# drv8353_based_bldc_driver_stage.net
KiCad netlist of a schematic drawn in EAGLE
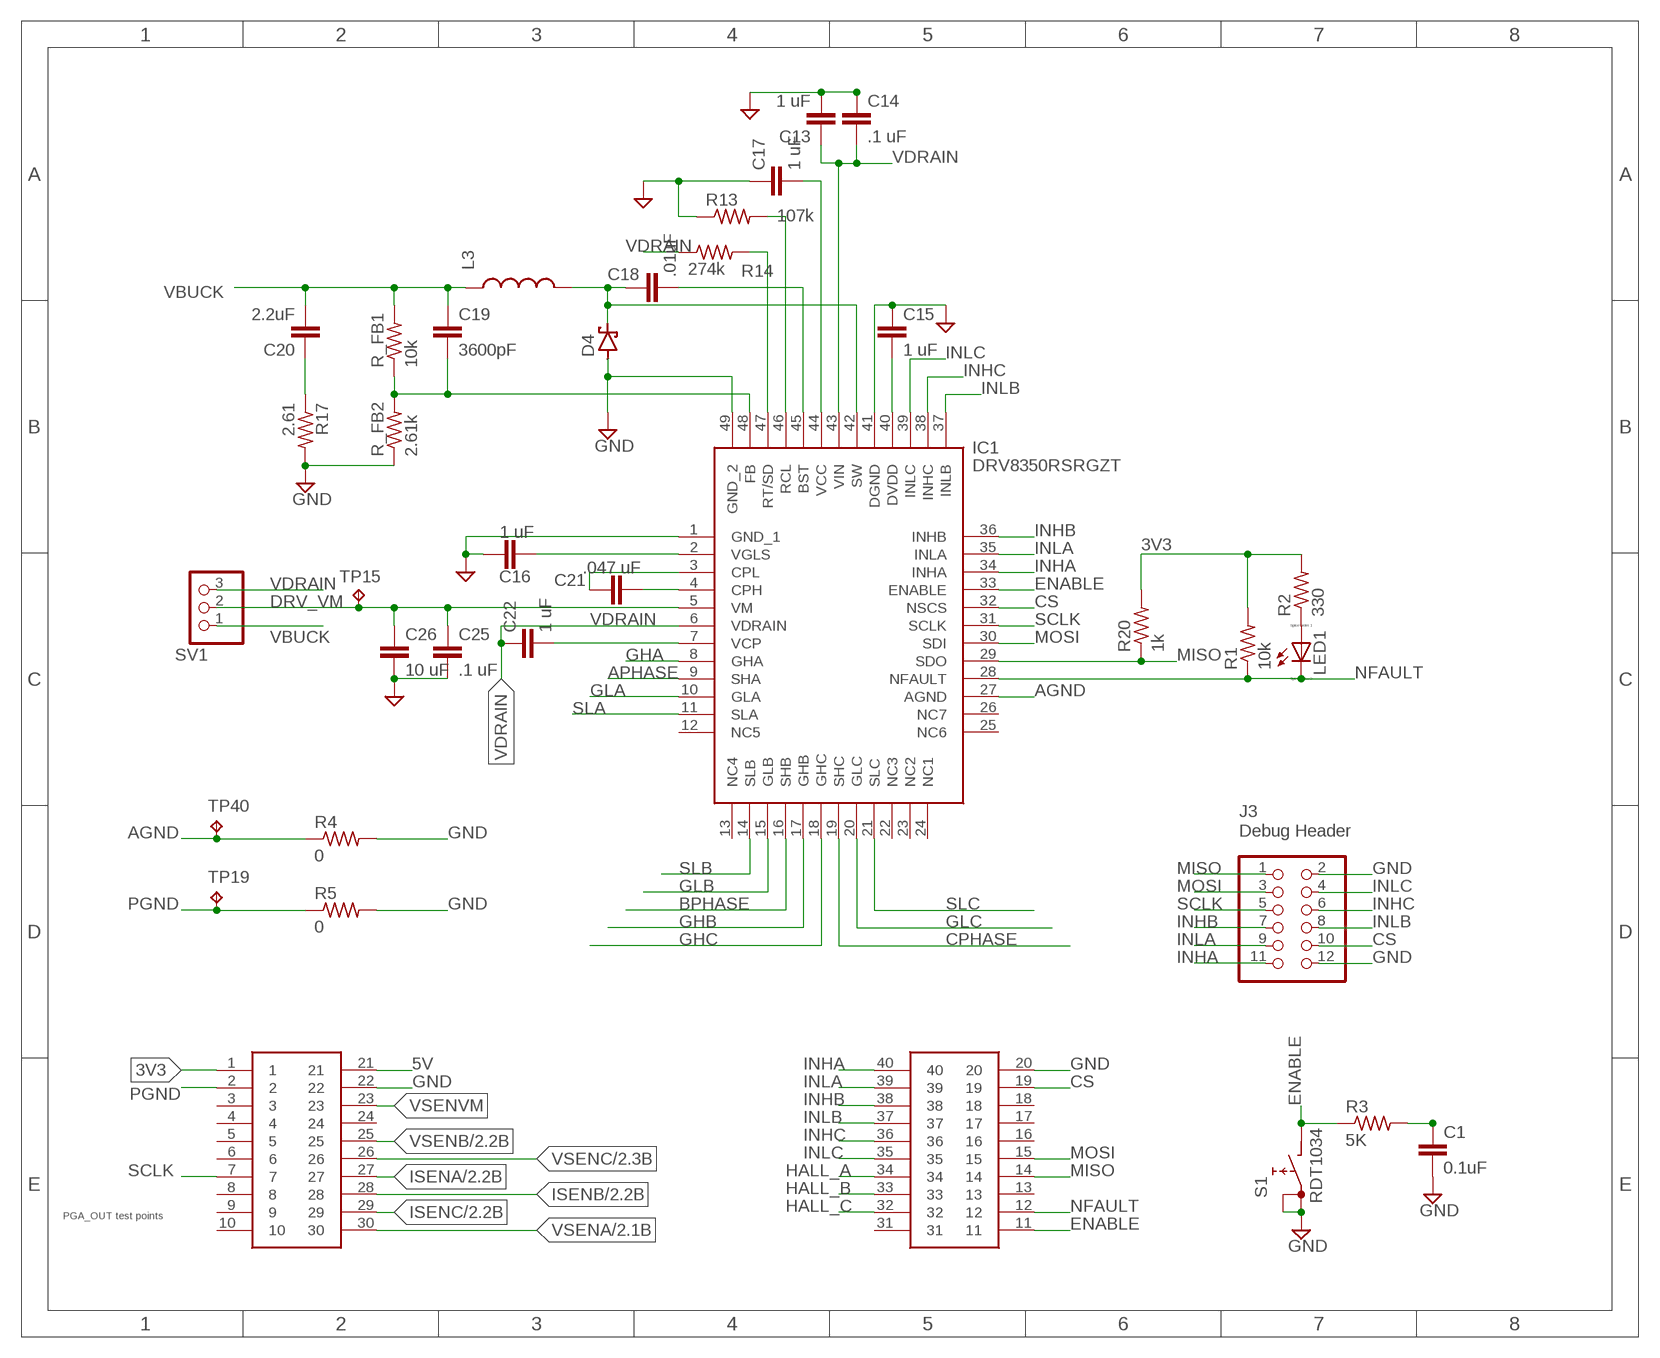
[diagram p0: schematic, sheet 1]
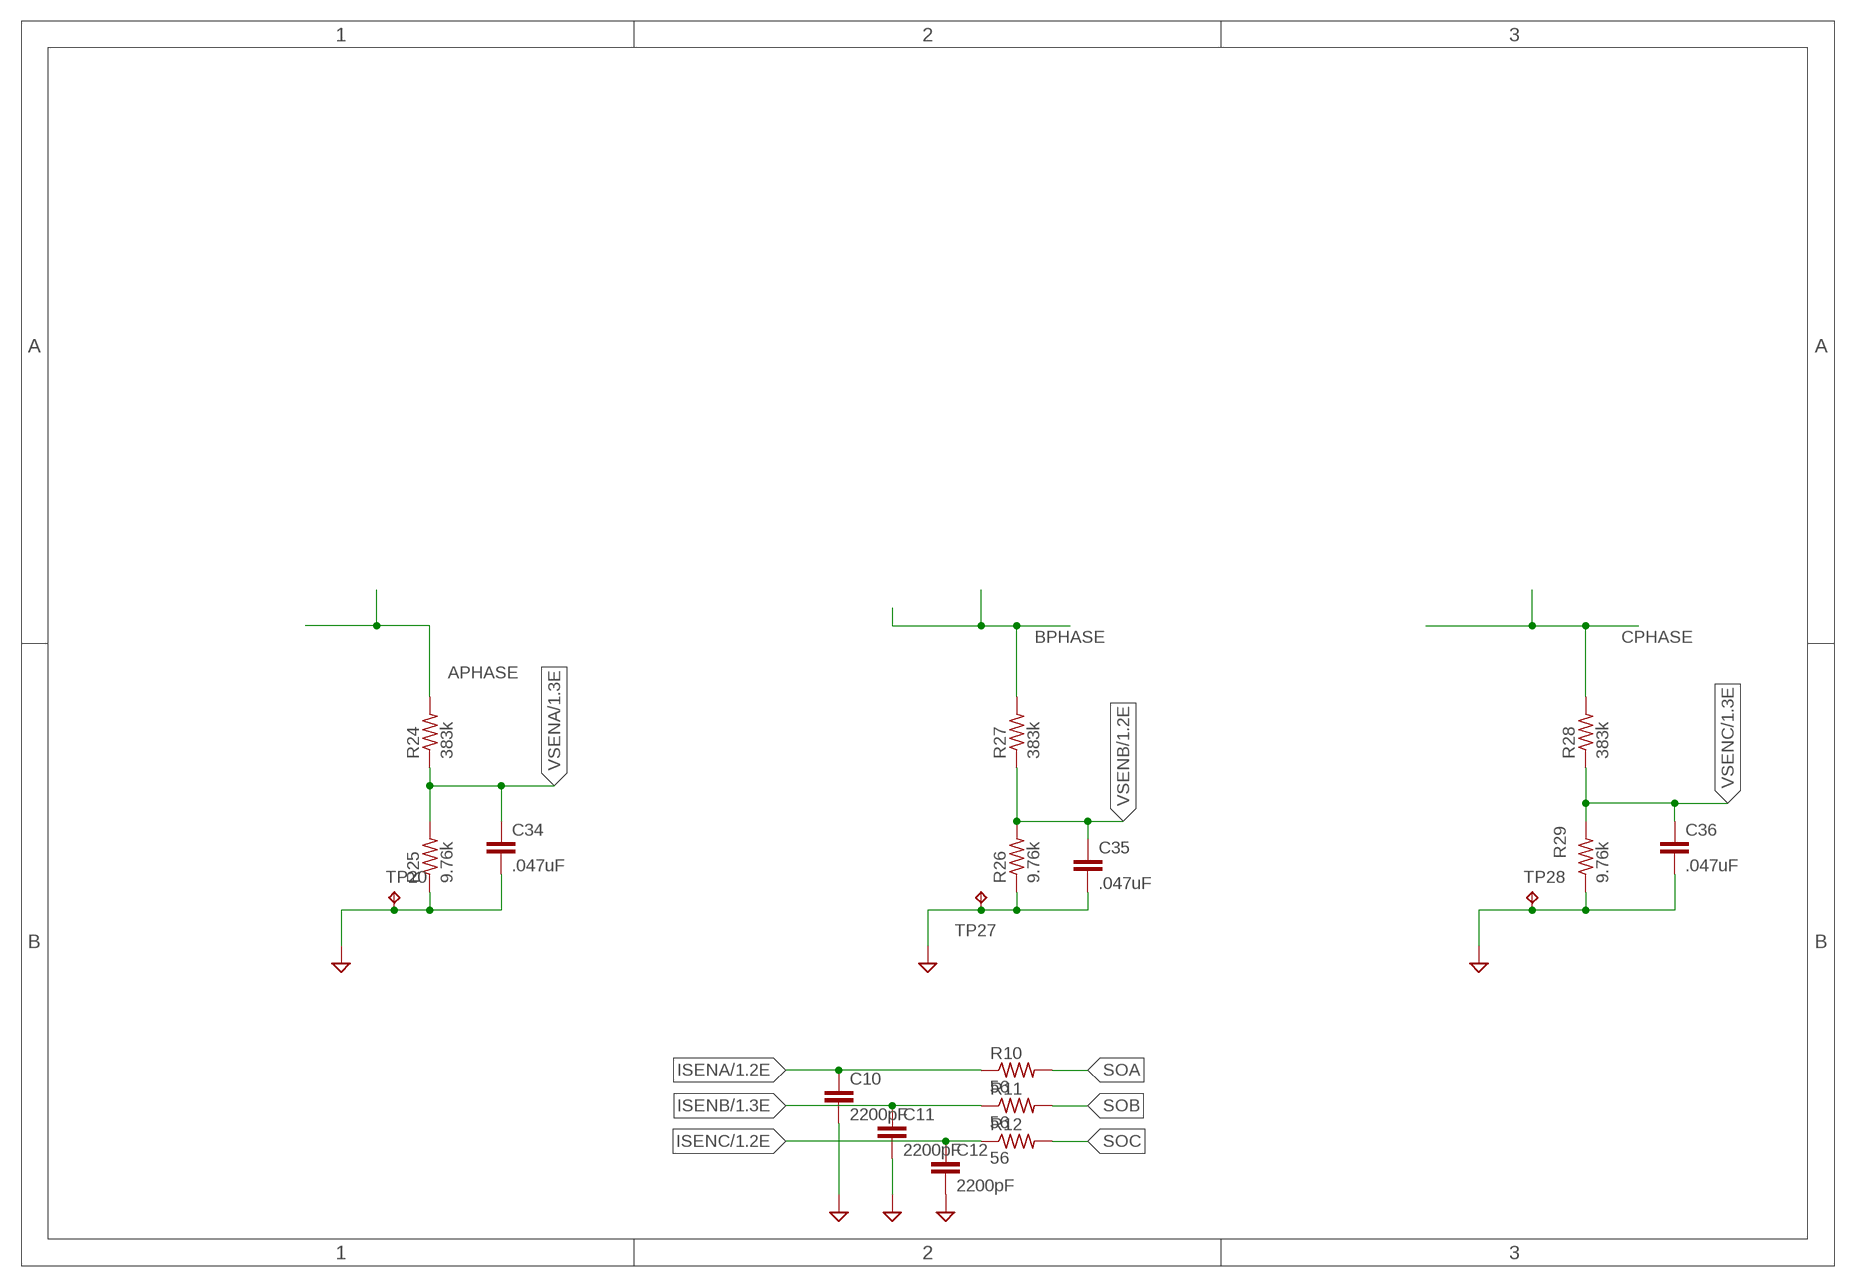
[diagram p1: schematic, sheet 2]
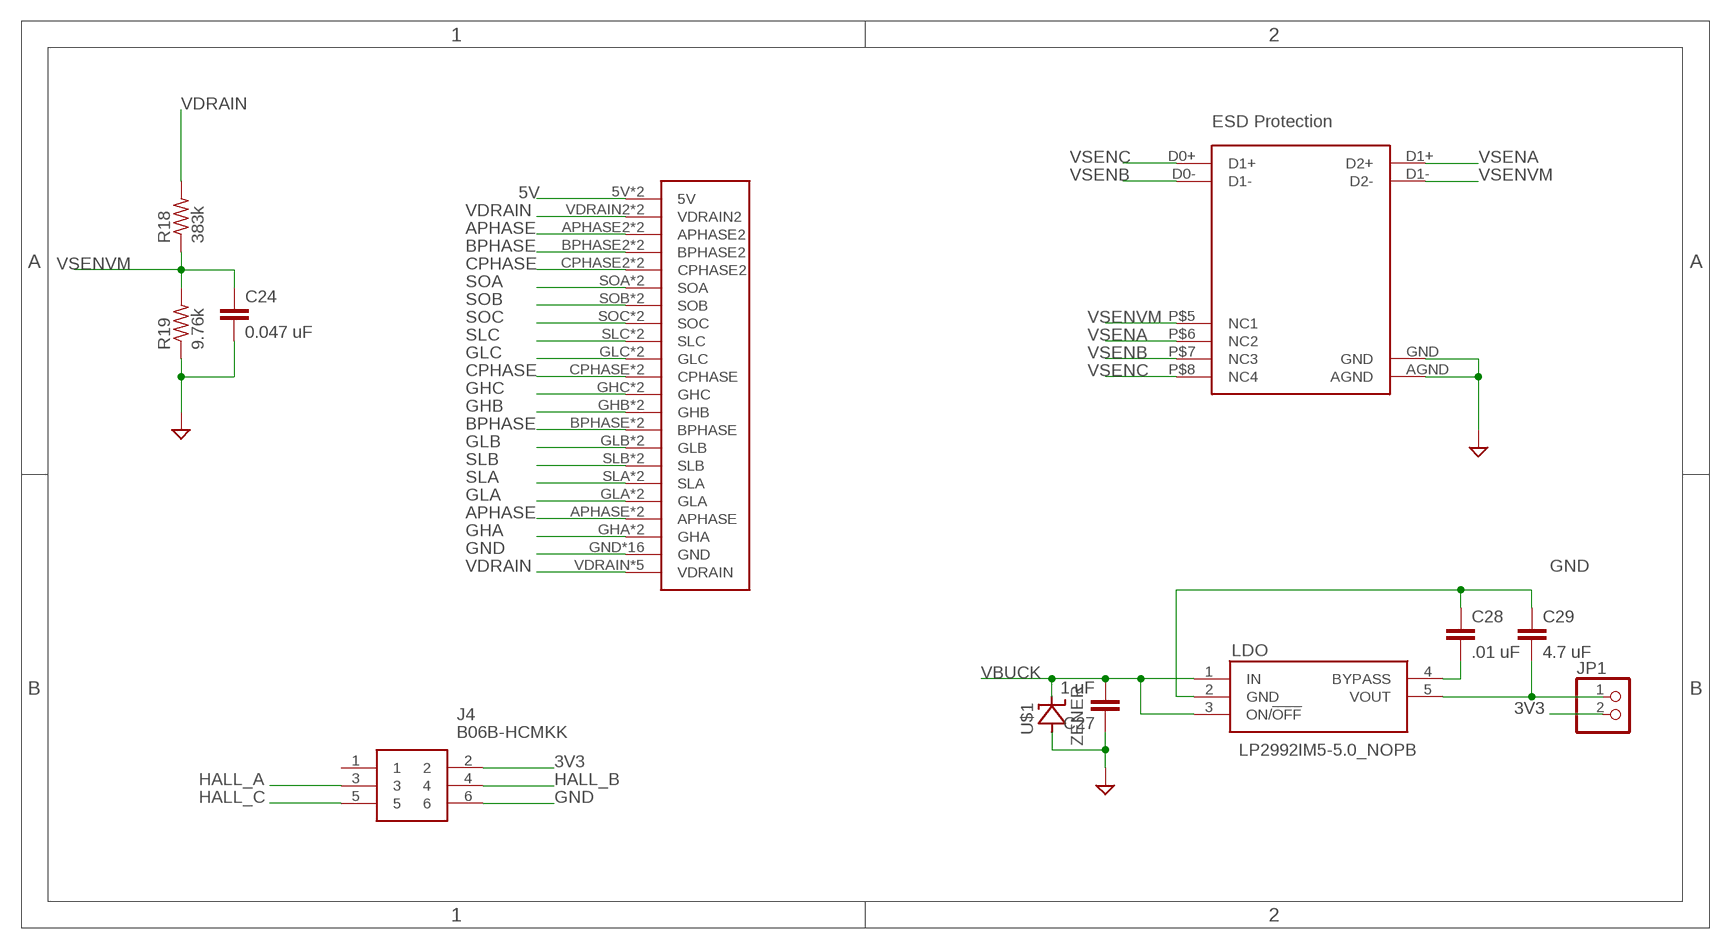
[diagram p2: schematic, sheet 3]

(export (version "E")
  (design (tool "Eeschema 10.0.6"))
  (components
    (comp (ref "C24")
      (value "0.047 uF")
      (footprint "eagle-import:C0603K")
      (libsource (lib "eagle-import") (part "C-EUC0603K"))
    )
    (comp (ref "C27")
      (value "1 uF")
      (footprint "eagle-import:C0805K")
      (libsource (lib "eagle-import") (part "C-EUC0805K"))
    )
    (comp (ref "C28")
      (value ".01 uF")
      (footprint "eagle-import:C0603K")
      (libsource (lib "eagle-import") (part "C-EUC0603K"))
    )
    (comp (ref "C29")
      (value "4.7 uF")
      (footprint "eagle-import:C1210K")
      (libsource (lib "eagle-import") (part "C-EUC1210K"))
    )
    (comp (ref "J4")
      (value "B06B-HCMKK")
      (footprint "eagle-import:B06BHCMKK")
      (fields (field (name "MOUSER_PART_NUMBER") "306-B06B-HCMKK"))
      (libsource (lib "eagle-import") (part "B06B-HCMKK"))
    )
    (comp (ref "JP1")
      (value "PINHD-1X2")
      (footprint "eagle-import:1X02")
      (libsource (lib "eagle-import") (part "PINHD-1X2"))
    )
    (comp (ref "LDO")
      (value "LP2992IM5-5.0_NOPB")
      (footprint "eagle-import:SOT95P280X145-5N")
      (fields
        (field (name "MANUFACTURER_PART_NUMBER") "LP2992IM5-5.0/NOPB")
        (field (name "MOUSER_PART_NUMBER") "926-2992IM5-5.0/NOPB")
      )
      (libsource (lib "eagle-import") (part "LP2992IM5-5.0_NOPB"))
    )
    (comp (ref "R18")
      (value "383k")
      (footprint "eagle-import:R0603")
      (libsource (lib "eagle-import") (part "R-US_R0603"))
    )
    (comp (ref "R19")
      (value "9.76k")
      (footprint "eagle-import:R0603")
      (libsource (lib "eagle-import") (part "R-US_R0603"))
    )
    (comp (ref "TVS_DIODE")
      (value "TPD4S010DQAR")
      (footprint "eagle-import:TPD4S010DQAR")
      (libsource (lib "eagle-import") (part "TPD4S010DQAR"))
    )
    (comp (ref "U$1")
      (value "ZENER")
      (footprint "eagle-import:SOD123")
      (libsource (lib "eagle-import") (part "ZENER"))
    )
    (comp (ref "U$3")
      (value "DRIVER_STAGE_CONNECTORDRIVER")
      (footprint "eagle-import:DRIVER_STAGE_CONNECTION")
      (libsource (lib "eagle-import") (part "DRIVER_STAGE_CONNECTORDRIVER"))
    )
    (comp (ref "C10")
      (value "2200pF")
      (footprint "eagle-import:C0603K")
      (libsource (lib "eagle-import") (part "C-EUC0603K"))
    )
    (comp (ref "C11")
      (value "2200pF")
      (footprint "eagle-import:C0603K")
      (libsource (lib "eagle-import") (part "C-EUC0603K"))
    )
    (comp (ref "C12")
      (value "2200pF")
      (footprint "eagle-import:C0603K")
      (libsource (lib "eagle-import") (part "C-EUC0603K"))
    )
    (comp (ref "C34")
      (value ".047uF")
      (footprint "eagle-import:C0603K")
      (libsource (lib "eagle-import") (part "C-EUC0603K"))
    )
    (comp (ref "C35")
      (value ".047uF")
      (footprint "eagle-import:C0603K")
      (libsource (lib "eagle-import") (part "C-EUC0603K"))
    )
    (comp (ref "C36")
      (value ".047uF")
      (footprint "eagle-import:C0603K")
      (libsource (lib "eagle-import") (part "C-EUC0603K"))
    )
    (comp (ref "R10")
      (value "56")
      (footprint "eagle-import:R0603")
      (libsource (lib "eagle-import") (part "R-US_R0603"))
    )
    (comp (ref "R11")
      (value "56")
      (footprint "eagle-import:R0603")
      (libsource (lib "eagle-import") (part "R-US_R0603"))
    )
    (comp (ref "R12")
      (value "56")
      (footprint "eagle-import:R0603")
      (libsource (lib "eagle-import") (part "R-US_R0603"))
    )
    (comp (ref "R24")
      (value "383k")
      (footprint "eagle-import:R0603")
      (libsource (lib "eagle-import") (part "R-US_R0603"))
    )
    (comp (ref "R25")
      (value "9.76k")
      (footprint "eagle-import:R0603")
      (libsource (lib "eagle-import") (part "R-US_R0603"))
    )
    (comp (ref "R26")
      (value "9.76k")
      (footprint "eagle-import:R0603")
      (libsource (lib "eagle-import") (part "R-US_R0603"))
    )
    (comp (ref "R27")
      (value "383k")
      (footprint "eagle-import:R0603")
      (libsource (lib "eagle-import") (part "R-US_R0603"))
    )
    (comp (ref "R28")
      (value "383k")
      (footprint "eagle-import:R0603")
      (libsource (lib "eagle-import") (part "R-US_R0603"))
    )
    (comp (ref "R29")
      (value "9.76k")
      (footprint "eagle-import:R0603")
      (libsource (lib "eagle-import") (part "R-US_R0603"))
    )
    (comp (ref "TP20")
      (value "TPB1,27")
      (footprint "eagle-import:B1,27")
      (libsource (lib "eagle-import") (part "TPB1,27"))
    )
    (comp (ref "TP27")
      (value "TPB1,27")
      (footprint "eagle-import:B1,27")
      (libsource (lib "eagle-import") (part "TPB1,27"))
    )
    (comp (ref "TP28")
      (value "TPB1,27")
      (footprint "eagle-import:B1,27")
      (libsource (lib "eagle-import") (part "TPB1,27"))
    )
    (comp (ref "C1")
      (value "0.1uF")
      (footprint "eagle-import:C0603K")
      (libsource (lib "eagle-import") (part "resistor_348_C-EUC0603K"))
    )
    (comp (ref "C13")
      (value "1 uF")
      (footprint "eagle-import:C1206K")
      (libsource (lib "eagle-import") (part "C-EUC1206K"))
    )
    (comp (ref "C14")
      (value ".1 uF")
      (footprint "eagle-import:C0805K")
      (libsource (lib "eagle-import") (part "resistor_348_C-EUC0805K"))
    )
    (comp (ref "C15")
      (value "1 uF")
      (footprint "eagle-import:C0603K")
      (libsource (lib "eagle-import") (part "C-EUC0603K"))
    )
    (comp (ref "C16")
      (value "1 uF")
      (footprint "eagle-import:C0603K")
      (libsource (lib "eagle-import") (part "C-EUC0603K"))
    )
    (comp (ref "C17")
      (value "1 uF")
      (footprint "eagle-import:C0603K")
      (libsource (lib "eagle-import") (part "C-EUC0603K"))
    )
    (comp (ref "C18")
      (value ".01uF")
      (footprint "eagle-import:C0603K")
      (libsource (lib "eagle-import") (part "C-EUC0603K"))
    )
    (comp (ref "C19")
      (value "3600pF")
      (footprint "eagle-import:C0603K")
      (libsource (lib "eagle-import") (part "C-EUC0603K"))
    )
    (comp (ref "C20")
      (value "2.2uF")
      (footprint "eagle-import:C0805K")
      (libsource (lib "eagle-import") (part "C-EUC0805K"))
    )
    (comp (ref "C21")
      (value ".047 uF")
      (footprint "eagle-import:C0805K")
      (libsource (lib "eagle-import") (part "C-EUC0805K"))
    )
    (comp (ref "C22")
      (value "1 uF")
      (footprint "eagle-import:C0603K")
      (libsource (lib "eagle-import") (part "resistor_348_C-EUC0603K"))
    )
    (comp (ref "C25")
      (value ".1 uF")
      (footprint "eagle-import:C0805K")
      (libsource (lib "eagle-import") (part "C-EUC0805K"))
    )
    (comp (ref "C26")
      (value "10 uF")
      (footprint "eagle-import:C2220K")
      (libsource (lib "eagle-import") (part "C-EUC2220K"))
    )
    (comp (ref "D4")
      (value "DFLS1200")
      (footprint "eagle-import:DFLS1200")
      (fields (field (name "SPICEPREFIX") "B"))
      (libsource (lib "eagle-import") (part "DFLS1200"))
    )
    (comp (ref "IC1")
      (value "DRV8350RSRGZT")
      (footprint "eagle-import:QFN50P700X700X100-49N")
      (fields
        (field (name "MANUFACTURER_PART_NUMBER") "DRV8353RSRGZT")
        (field (name "MOUSER_PART_NUMBER") "595-DRV8353RSRGZT")
      )
      (libsource (lib "eagle-import") (part "DRV8350RSRGZT"))
    )
    (comp (ref "J3")
      (value "2X6 FEMALE")
      (footprint "eagle-import:2X06")
      (libsource (lib "eagle-import") (part "PINHD-2X6"))
    )
    (comp (ref "L3")
      (value "330 uH")
      (footprint "eagle-import:74404084331")
      (libsource (lib "eagle-import") (part "74404084331"))
    )
    (comp (ref "LED1")
      (value "LED_ESML0603")
      (footprint "eagle-import:LED_SML0603")
      (libsource (lib "eagle-import") (part "LED_ESML0603"))
    )
    (comp (ref "R1")
      (value "10k")
      (footprint "eagle-import:R0603")
      (libsource (lib "eagle-import") (part "R-US_R0603"))
    )
    (comp (ref "R2")
      (value "330")
      (footprint "eagle-import:R0603")
      (libsource (lib "eagle-import") (part "R-US_R0603"))
    )
    (comp (ref "R3")
      (value "5K")
      (footprint "eagle-import:R0603")
      (libsource (lib "eagle-import") (part "resistor_348_R-US_R0603"))
    )
    (comp (ref "R4")
      (value "0")
      (footprint "eagle-import:R0603")
      (libsource (lib "eagle-import") (part "resistor_348_R-US_R0603"))
    )
    (comp (ref "R5")
      (value "0")
      (footprint "eagle-import:R0603")
      (libsource (lib "eagle-import") (part "resistor_348_R-US_R0603"))
    )
    (comp (ref "R13")
      (value "107k")
      (footprint "eagle-import:R0603")
      (libsource (lib "eagle-import") (part "R-US_R0603"))
    )
    (comp (ref "R14")
      (value "274k")
      (footprint "eagle-import:R0603")
      (libsource (lib "eagle-import") (part "R-US_R0603"))
    )
    (comp (ref "R17")
      (value "2.61")
      (footprint "eagle-import:R0603")
      (libsource (lib "eagle-import") (part "R-US_R0603"))
    )
    (comp (ref "R20")
      (value "1k")
      (footprint "eagle-import:R0603")
      (libsource (lib "eagle-import") (part "R-US_R0603"))
    )
    (comp (ref "R_FB1")
      (value "10k")
      (footprint "eagle-import:R0603")
      (libsource (lib "eagle-import") (part "R-US_R0603"))
    )
    (comp (ref "R_FB2")
      (value "2.61k")
      (footprint "eagle-import:R0603")
      (libsource (lib "eagle-import") (part "R-US_R0603"))
    )
    (comp (ref "S1")
      (value "RDT1034")
      (footprint "eagle-import:RDT1034")
      (libsource (lib "eagle-import") (part "RDT1034"))
    )
    (comp (ref "SV1")
      (value "PINHD-1X3")
      (footprint "eagle-import:1X03")
      (libsource (lib "eagle-import") (part "PINHD-1X3"))
    )
    (comp (ref "TP15")
      (value "TPB1,27")
      (footprint "eagle-import:B1,27")
      (libsource (lib "eagle-import") (part "TPB1,27"))
    )
    (comp (ref "TP19")
      (value "TPB1,27")
      (footprint "eagle-import:B1,27")
      (libsource (lib "eagle-import") (part "TPB1,27"))
    )
    (comp (ref "TP40")
      (value "TPB1,27")
      (footprint "eagle-import:B1,27")
      (libsource (lib "eagle-import") (part "TPB1,27"))
    )
    (comp (ref "U$2")
      (value "BOOSTER_DOCK")
      (footprint "eagle-import:BOOSTER_DOCK")
      (libsource (lib "eagle-import") (part "BOOSTER_DOCK"))
    )
  )
  (nets
    (net (code "1") (name "3V3") (class "Default")
      (node (ref "J4") (pin "2") (pinfunction "2_2") (pintype "bidirectional"))
      (node (ref "JP1") (pin "2") (pinfunction "2_2") (pintype "passive"))
      (node (ref "R1") (pin "2") (pinfunction "2_2") (pintype "passive"))
      (node (ref "R2") (pin "2") (pinfunction "2_2") (pintype "passive"))
      (node (ref "R20") (pin "2") (pinfunction "2_2") (pintype "passive"))
      (node (ref "U$2") (pin "1") (pinfunction "1_1") (pintype "bidirectional"))
    )
    (net (code "2") (name "5V") (class "Default")
      (node (ref "U$2") (pin "21") (pinfunction "21_21") (pintype "bidirectional"))
      (node (ref "U$3") (pin "5V") (pinfunction "5V_5V") (pintype "bidirectional"))
      (node (ref "U$3") (pin "5VH") (pinfunction "5V_5VH") (pintype "bidirectional"))
    )
    (net (code "3") (name "AGND") (class "Default")
      (node (ref "IC1") (pin "27") (pinfunction "AGND_27") (pintype "bidirectional"))
      (node (ref "R4") (pin "1") (pinfunction "1_1") (pintype "passive"))
      (node (ref "TP40") (pin "TP") (pinfunction "TP_TP") (pintype "input"))
    )
    (net (code "4") (name "APHASE") (class "Default")
      (node (ref "IC1") (pin "9") (pinfunction "SHA_9") (pintype "bidirectional"))
      (node (ref "R24") (pin "2") (pinfunction "2_2") (pintype "passive"))
      (node (ref "U$3") (pin "APHASE") (pinfunction "APHASE_APHASE") (pintype "bidirectional"))
      (node (ref "U$3") (pin "APHASE2") (pinfunction "APHASE2_APHASE2") (pintype "bidirectional"))
      (node (ref "U$3") (pin "APHASE2H") (pinfunction "APHASE2_APHASE2H") (pintype "bidirectional"))
      (node (ref "U$3") (pin "APHASEH") (pinfunction "APHASE_APHASEH") (pintype "bidirectional"))
    )
    (net (code "5") (name "BPHASE") (class "Default")
      (node (ref "IC1") (pin "16") (pinfunction "SHB_16") (pintype "bidirectional"))
      (node (ref "R27") (pin "2") (pinfunction "2_2") (pintype "passive"))
      (node (ref "U$3") (pin "BPHASE") (pinfunction "BPHASE_BPHASE") (pintype "bidirectional"))
      (node (ref "U$3") (pin "BPHASE2") (pinfunction "BPHASE2_BPHASE2") (pintype "bidirectional"))
      (node (ref "U$3") (pin "BPHASE2H") (pinfunction "BPHASE2_BPHASE2H") (pintype "bidirectional"))
      (node (ref "U$3") (pin "BPHASEH") (pinfunction "BPHASE_BPHASEH") (pintype "bidirectional"))
    )
    (net (code "6") (name "CPHASE") (class "Default")
      (node (ref "IC1") (pin "19") (pinfunction "SHC_19") (pintype "bidirectional"))
      (node (ref "R28") (pin "2") (pinfunction "2_2") (pintype "passive"))
      (node (ref "U$3") (pin "CPHASE") (pinfunction "CPHASE_CPHASE") (pintype "bidirectional"))
      (node (ref "U$3") (pin "CPHASE2") (pinfunction "CPHASE2_CPHASE2") (pintype "bidirectional"))
      (node (ref "U$3") (pin "CPHASE2H") (pinfunction "CPHASE2_CPHASE2H") (pintype "bidirectional"))
      (node (ref "U$3") (pin "CPHASEH") (pinfunction "CPHASE_CPHASEH") (pintype "bidirectional"))
    )
    (net (code "7") (name "CS") (class "Default")
      (node (ref "IC1") (pin "32") (pinfunction "NSCS_32") (pintype "bidirectional"))
      (node (ref "J3") (pin "10") (pinfunction "10_10") (pintype "passive"))
      (node (ref "U$2") (pin "19") (pinfunction "19_19") (pintype "bidirectional"))
    )
    (net (code "8") (name "DRV_VM") (class "Default")
      (node (ref "C25") (pin "1") (pinfunction "1_1") (pintype "passive"))
      (node (ref "C26") (pin "1") (pinfunction "1_1") (pintype "passive"))
      (node (ref "IC1") (pin "5") (pinfunction "VM_5") (pintype "bidirectional"))
      (node (ref "SV1") (pin "2") (pinfunction "2_2") (pintype "passive"))
      (node (ref "TP15") (pin "TP") (pinfunction "TP_TP") (pintype "input"))
    )
    (net (code "9") (name "ENABLE") (class "Default")
      (node (ref "IC1") (pin "33") (pinfunction "ENABLE_33") (pintype "bidirectional"))
      (node (ref "R3") (pin "1") (pinfunction "1_1") (pintype "passive"))
      (node (ref "S1") (pin "B") (pinfunction "B_B") (pintype "passive"))
      (node (ref "U$2") (pin "11") (pinfunction "11_11") (pintype "bidirectional"))
    )
    (net (code "10") (name "GHA") (class "Default")
      (node (ref "IC1") (pin "8") (pinfunction "GHA_8") (pintype "bidirectional"))
      (node (ref "U$3") (pin "GHA") (pinfunction "GHA_GHA") (pintype "bidirectional"))
      (node (ref "U$3") (pin "GHAH") (pinfunction "GHA_GHAH") (pintype "bidirectional"))
    )
    (net (code "11") (name "GHB") (class "Default")
      (node (ref "IC1") (pin "17") (pinfunction "GHB_17") (pintype "bidirectional"))
      (node (ref "U$3") (pin "GHB") (pinfunction "GHB_GHB") (pintype "bidirectional"))
      (node (ref "U$3") (pin "GHBH") (pinfunction "GHB_GHBH") (pintype "bidirectional"))
    )
    (net (code "12") (name "GHC") (class "Default")
      (node (ref "IC1") (pin "18") (pinfunction "GHC_18") (pintype "bidirectional"))
      (node (ref "U$3") (pin "GHC") (pinfunction "GHC_GHC") (pintype "bidirectional"))
      (node (ref "U$3") (pin "GHCH") (pinfunction "GHC_GHCH") (pintype "bidirectional"))
    )
    (net (code "13") (name "GLA") (class "Default")
      (node (ref "IC1") (pin "10") (pinfunction "GLA_10") (pintype "bidirectional"))
      (node (ref "U$3") (pin "GLA") (pinfunction "GLA_GLA") (pintype "bidirectional"))
      (node (ref "U$3") (pin "GLAH") (pinfunction "GLA_GLAH") (pintype "bidirectional"))
    )
    (net (code "14") (name "GLB") (class "Default")
      (node (ref "IC1") (pin "15") (pinfunction "GLB_15") (pintype "bidirectional"))
      (node (ref "U$3") (pin "GLB") (pinfunction "GLB_GLB") (pintype "bidirectional"))
      (node (ref "U$3") (pin "GLBH") (pinfunction "GLB_GLBH") (pintype "bidirectional"))
    )
    (net (code "15") (name "GLC") (class "Default")
      (node (ref "IC1") (pin "20") (pinfunction "GLC_20") (pintype "bidirectional"))
      (node (ref "U$3") (pin "GLC") (pinfunction "GLC_GLC") (pintype "bidirectional"))
      (node (ref "U$3") (pin "GLCH") (pinfunction "GLC_GLCH") (pintype "bidirectional"))
    )
    (net (code "16") (name "GND") (class "Default")
      (node (ref "C1") (pin "2") (pinfunction "2_2") (pintype "passive"))
      (node (ref "C10") (pin "2") (pinfunction "2_2") (pintype "passive"))
      (node (ref "C11") (pin "2") (pinfunction "2_2") (pintype "passive"))
      (node (ref "C12") (pin "2") (pinfunction "2_2") (pintype "passive"))
      (node (ref "C13") (pin "2") (pinfunction "2_2") (pintype "passive"))
      (node (ref "C14") (pin "1") (pinfunction "1_1") (pintype "passive"))
      (node (ref "C15") (pin "1") (pinfunction "1_1") (pintype "passive"))
      (node (ref "C16") (pin "1") (pinfunction "1_1") (pintype "passive"))
      (node (ref "C17") (pin "1") (pinfunction "1_1") (pintype "passive"))
      (node (ref "C24") (pin "2") (pinfunction "2_2") (pintype "passive"))
      (node (ref "C25") (pin "2") (pinfunction "2_2") (pintype "passive"))
      (node (ref "C26") (pin "2") (pinfunction "2_2") (pintype "passive"))
      (node (ref "C27") (pin "1") (pinfunction "1_1") (pintype "passive"))
      (node (ref "C28") (pin "1") (pinfunction "1_1") (pintype "passive"))
      (node (ref "C29") (pin "1") (pinfunction "1_1") (pintype "passive"))
      (node (ref "C34") (pin "2") (pinfunction "2_2") (pintype "passive"))
      (node (ref "C35") (pin "2") (pinfunction "2_2") (pintype "passive"))
      (node (ref "C36") (pin "2") (pinfunction "2_2") (pintype "passive"))
      (node (ref "D4") (pin "GND") (pinfunction "GND_GND") (pintype "passive"))
      (node (ref "IC1") (pin "1") (pinfunction "GND_1_1") (pintype "bidirectional"))
      (node (ref "IC1") (pin "41") (pinfunction "DGND_41") (pintype "bidirectional"))
      (node (ref "IC1") (pin "49") (pinfunction "GND_2_49") (pintype "bidirectional"))
      (node (ref "J3") (pin "12") (pinfunction "12_12") (pintype "passive"))
      (node (ref "J3") (pin "2") (pinfunction "2_2") (pintype "passive"))
      (node (ref "J4") (pin "6") (pinfunction "6_6") (pintype "bidirectional"))
      (node (ref "LDO") (pin "2") (pinfunction "GND_2") (pintype "power_in"))
      (node (ref "R13") (pin "1") (pinfunction "1_1") (pintype "passive"))
      (node (ref "R17") (pin "2") (pinfunction "2_2") (pintype "passive"))
      (node (ref "R19") (pin "1") (pinfunction "1_1") (pintype "passive"))
      (node (ref "R25") (pin "1") (pinfunction "1_1") (pintype "passive"))
      (node (ref "R26") (pin "1") (pinfunction "1_1") (pintype "passive"))
      (node (ref "R29") (pin "1") (pinfunction "1_1") (pintype "passive"))
      (node (ref "R4") (pin "2") (pinfunction "2_2") (pintype "passive"))
      (node (ref "R5") (pin "2") (pinfunction "2_2") (pintype "passive"))
      (node (ref "R_FB2") (pin "1") (pinfunction "1_1") (pintype "passive"))
      (node (ref "S1") (pin "A") (pinfunction "A_A") (pintype "passive"))
      (node (ref "S1") (pin "A1") (pinfunction "A1_A1") (pintype "passive"))
      (node (ref "TP20") (pin "TP") (pinfunction "TP_TP") (pintype "input"))
      (node (ref "TP27") (pin "TP") (pinfunction "TP_TP") (pintype "input"))
      (node (ref "TP28") (pin "TP") (pinfunction "TP_TP") (pintype "input"))
      (node (ref "TVS_DIODE") (pin "AGND") (pinfunction "AGND_AGND") (pintype "bidirectional"))
      (node (ref "TVS_DIODE") (pin "GND") (pinfunction "GND_GND") (pintype "bidirectional"))
      (node (ref "U$1") (pin "2") (pinfunction "A_2") (pintype "passive"))
      (node (ref "U$2") (pin "20") (pinfunction "20_20") (pintype "bidirectional"))
      (node (ref "U$2") (pin "22") (pinfunction "22_22") (pintype "bidirectional"))
      (node (ref "U$3") (pin "GND") (pinfunction "GND_GND") (pintype "bidirectional"))
      (node (ref "U$3") (pin "GND2") (pinfunction "GND_GND2") (pintype "bidirectional"))
      (node (ref "U$3") (pin "GND2H1") (pinfunction "GND_GND2H1") (pintype "bidirectional"))
      (node (ref "U$3") (pin "GND2H10") (pinfunction "GND_GND2H10") (pintype "bidirectional"))
      (node (ref "U$3") (pin "GND2H2") (pinfunction "GND_GND2H2") (pintype "bidirectional"))
      (node (ref "U$3") (pin "GND2H3") (pinfunction "GND_GND2H3") (pintype "bidirectional"))
      (node (ref "U$3") (pin "GND2H4") (pinfunction "GND_GND2H4") (pintype "bidirectional"))
      (node (ref "U$3") (pin "GND2H5") (pinfunction "GND_GND2H5") (pintype "bidirectional"))
      (node (ref "U$3") (pin "GND2H6") (pinfunction "GND_GND2H6") (pintype "bidirectional"))
      (node (ref "U$3") (pin "GND2H7") (pinfunction "GND_GND2H7") (pintype "bidirectional"))
      (node (ref "U$3") (pin "GND2H8") (pinfunction "GND_GND2H8") (pintype "bidirectional"))
      (node (ref "U$3") (pin "GND2H9") (pinfunction "GND_GND2H9") (pintype "bidirectional"))
      (node (ref "U$3") (pin "GNDH1") (pinfunction "GND_GNDH1") (pintype "bidirectional"))
      (node (ref "U$3") (pin "GNDH2") (pinfunction "GND_GNDH2") (pintype "bidirectional"))
      (node (ref "U$3") (pin "GNDH3") (pinfunction "GND_GNDH3") (pintype "bidirectional"))
      (node (ref "U$3") (pin "GNDH4") (pinfunction "GND_GNDH4") (pintype "bidirectional"))
    )
    (net (code "17") (name "HALL_A") (class "Default")
      (node (ref "J4") (pin "3") (pinfunction "3_3") (pintype "bidirectional"))
      (node (ref "U$2") (pin "34") (pinfunction "34_34") (pintype "bidirectional"))
    )
    (net (code "18") (name "HALL_B") (class "Default")
      (node (ref "J4") (pin "4") (pinfunction "4_4") (pintype "bidirectional"))
      (node (ref "U$2") (pin "33") (pinfunction "33_33") (pintype "bidirectional"))
    )
    (net (code "19") (name "HALL_C") (class "Default")
      (node (ref "J4") (pin "5") (pinfunction "5_5") (pintype "bidirectional"))
      (node (ref "U$2") (pin "32") (pinfunction "32_32") (pintype "bidirectional"))
    )
    (net (code "20") (name "INHA") (class "Default")
      (node (ref "IC1") (pin "34") (pinfunction "INHA_34") (pintype "bidirectional"))
      (node (ref "J3") (pin "11") (pinfunction "11_11") (pintype "passive"))
      (node (ref "U$2") (pin "40") (pinfunction "40_40") (pintype "bidirectional"))
    )
    (net (code "21") (name "INHB") (class "Default")
      (node (ref "IC1") (pin "36") (pinfunction "INHB_36") (pintype "bidirectional"))
      (node (ref "J3") (pin "7") (pinfunction "7_7") (pintype "passive"))
      (node (ref "U$2") (pin "38") (pinfunction "38_38") (pintype "bidirectional"))
    )
    (net (code "22") (name "INHC") (class "Default")
      (node (ref "IC1") (pin "38") (pinfunction "INHC_38") (pintype "bidirectional"))
      (node (ref "J3") (pin "6") (pinfunction "6_6") (pintype "passive"))
      (node (ref "U$2") (pin "36") (pinfunction "36_36") (pintype "bidirectional"))
    )
    (net (code "23") (name "INLA") (class "Default")
      (node (ref "IC1") (pin "35") (pinfunction "INLA_35") (pintype "bidirectional"))
      (node (ref "J3") (pin "9") (pinfunction "9_9") (pintype "passive"))
      (node (ref "U$2") (pin "39") (pinfunction "39_39") (pintype "bidirectional"))
    )
    (net (code "24") (name "INLB") (class "Default")
      (node (ref "IC1") (pin "37") (pinfunction "INLB_37") (pintype "bidirectional"))
      (node (ref "J3") (pin "8") (pinfunction "8_8") (pintype "passive"))
      (node (ref "U$2") (pin "37") (pinfunction "37_37") (pintype "bidirectional"))
    )
    (net (code "25") (name "INLC") (class "Default")
      (node (ref "IC1") (pin "39") (pinfunction "INLC_39") (pintype "bidirectional"))
      (node (ref "J3") (pin "4") (pinfunction "4_4") (pintype "passive"))
      (node (ref "U$2") (pin "35") (pinfunction "35_35") (pintype "bidirectional"))
    )
    (net (code "26") (name "ISENA") (class "Default")
      (node (ref "C10") (pin "1") (pinfunction "1_1") (pintype "passive"))
      (node (ref "R10") (pin "1") (pinfunction "1_1") (pintype "passive"))
      (node (ref "U$2") (pin "27") (pinfunction "27_27") (pintype "bidirectional"))
    )
    (net (code "27") (name "ISENB") (class "Default")
      (node (ref "C11") (pin "1") (pinfunction "1_1") (pintype "passive"))
      (node (ref "R11") (pin "1") (pinfunction "1_1") (pintype "passive"))
      (node (ref "U$2") (pin "28") (pinfunction "28_28") (pintype "bidirectional"))
    )
    (net (code "28") (name "ISENC") (class "Default")
      (node (ref "C12") (pin "1") (pinfunction "1_1") (pintype "passive"))
      (node (ref "R12") (pin "1") (pinfunction "1_1") (pintype "passive"))
      (node (ref "U$2") (pin "29") (pinfunction "29_29") (pintype "bidirectional"))
    )
    (net (code "29") (name "MISO") (class "Default")
      (node (ref "IC1") (pin "29") (pinfunction "SDO_29") (pintype "bidirectional"))
      (node (ref "J3") (pin "1") (pinfunction "1_1") (pintype "passive"))
      (node (ref "R20") (pin "1") (pinfunction "1_1") (pintype "passive"))
      (node (ref "U$2") (pin "14") (pinfunction "14_14") (pintype "bidirectional"))
    )
    (net (code "30") (name "MOSI") (class "Default")
      (node (ref "IC1") (pin "30") (pinfunction "SDI_30") (pintype "bidirectional"))
      (node (ref "J3") (pin "3") (pinfunction "3_3") (pintype "passive"))
      (node (ref "U$2") (pin "15") (pinfunction "15_15") (pintype "bidirectional"))
    )
    (net (code "31") (name "NFAULT") (class "Default")
      (node (ref "IC1") (pin "28") (pinfunction "NFAULT_28") (pintype "bidirectional"))
      (node (ref "LED1") (pin "C") (pinfunction "C_C") (pintype "passive"))
      (node (ref "R1") (pin "1") (pinfunction "1_1") (pintype "passive"))
      (node (ref "U$2") (pin "12") (pinfunction "12_12") (pintype "bidirectional"))
    )
    (net (code "32") (name "Net-(C1-Pad1)") (class "Default")
      (node (ref "C1") (pin "1") (pinfunction "1_1") (pintype "passive"))
      (node (ref "R3") (pin "2") (pinfunction "2_2") (pintype "passive"))
    )
    (net (code "33") (name "Net-(C20-Pad1)") (class "Default")
      (node (ref "C20") (pin "1") (pinfunction "1_1") (pintype "passive"))
      (node (ref "R17") (pin "1") (pinfunction "1_1") (pintype "passive"))
    )
    (net (code "34") (name "Net-(IC1-BST)") (class "Default")
      (node (ref "C18") (pin "2") (pinfunction "2_2") (pintype "passive"))
      (node (ref "IC1") (pin "45") (pinfunction "BST_45") (pintype "bidirectional"))
    )
    (net (code "35") (name "Net-(IC1-CPH)") (class "Default")
      (node (ref "C21") (pin "2") (pinfunction "2_2") (pintype "passive"))
      (node (ref "IC1") (pin "4") (pinfunction "CPH_4") (pintype "bidirectional"))
    )
    (net (code "36") (name "Net-(IC1-CPL)") (class "Default")
      (node (ref "C21") (pin "1") (pinfunction "1_1") (pintype "passive"))
      (node (ref "IC1") (pin "3") (pinfunction "CPL_3") (pintype "bidirectional"))
    )
    (net (code "37") (name "Net-(IC1-DVDD)") (class "Default")
      (node (ref "C15") (pin "2") (pinfunction "2_2") (pintype "passive"))
      (node (ref "IC1") (pin "40") (pinfunction "DVDD_40") (pintype "bidirectional"))
    )
    (net (code "38") (name "Net-(IC1-FB)") (class "Default")
      (node (ref "C19") (pin "2") (pinfunction "2_2") (pintype "passive"))
      (node (ref "IC1") (pin "48") (pinfunction "FB_48") (pintype "bidirectional"))
      (node (ref "R_FB1") (pin "1") (pinfunction "1_1") (pintype "passive"))
      (node (ref "R_FB2") (pin "2") (pinfunction "2_2") (pintype "passive"))
    )
    (net (code "39") (name "Net-(IC1-RCL)") (class "Default")
      (node (ref "IC1") (pin "46") (pinfunction "RCL_46") (pintype "bidirectional"))
      (node (ref "R13") (pin "2") (pinfunction "2_2") (pintype "passive"))
    )
    (net (code "40") (name "Net-(IC1-RT{slash}SD)") (class "Default")
      (node (ref "IC1") (pin "47") (pinfunction "RT/SD_47") (pintype "bidirectional"))
      (node (ref "R14") (pin "2") (pinfunction "2_2") (pintype "passive"))
    )
    (net (code "41") (name "Net-(IC1-SW)") (class "Default")
      (node (ref "C18") (pin "1") (pinfunction "1_1") (pintype "passive"))
      (node (ref "D4") (pin "LINE") (pinfunction "LINE_LINE") (pintype "passive"))
      (node (ref "IC1") (pin "42") (pinfunction "SW_42") (pintype "bidirectional"))
      (node (ref "L3") (pin "P$2") (pinfunction "2_P$2") (pintype "passive"))
    )
    (net (code "42") (name "Net-(IC1-VCC)") (class "Default")
      (node (ref "C17") (pin "2") (pinfunction "2_2") (pintype "passive"))
      (node (ref "IC1") (pin "44") (pinfunction "VCC_44") (pintype "bidirectional"))
    )
    (net (code "43") (name "Net-(IC1-VCP)") (class "Default")
      (node (ref "C22") (pin "2") (pinfunction "2_2") (pintype "passive"))
      (node (ref "IC1") (pin "7") (pinfunction "VCP_7") (pintype "bidirectional"))
    )
    (net (code "44") (name "Net-(IC1-VGLS)") (class "Default")
      (node (ref "C16") (pin "2") (pinfunction "2_2") (pintype "passive"))
      (node (ref "IC1") (pin "2") (pinfunction "VGLS_2") (pintype "bidirectional"))
    )
    (net (code "45") (name "Net-(LDO-BYPASS)") (class "Default")
      (node (ref "C28") (pin "2") (pinfunction "2_2") (pintype "passive"))
      (node (ref "LDO") (pin "4") (pinfunction "BYPASS_4") (pintype "bidirectional"))
    )
    (net (code "46") (name "Net-(LDO-VOUT)") (class "Default")
      (node (ref "C29") (pin "2") (pinfunction "2_2") (pintype "passive"))
      (node (ref "JP1") (pin "1") (pinfunction "1_1") (pintype "passive"))
      (node (ref "LDO") (pin "5") (pinfunction "VOUT_5") (pintype "output"))
    )
    (net (code "47") (name "Net-(LED1-PadA)") (class "Default")
      (node (ref "LED1") (pin "A") (pinfunction "A_A") (pintype "passive"))
      (node (ref "R2") (pin "1") (pinfunction "1_1") (pintype "passive"))
    )
    (net (code "48") (name "PGND") (class "Default")
      (node (ref "R5") (pin "1") (pinfunction "1_1") (pintype "passive"))
      (node (ref "TP19") (pin "TP") (pinfunction "TP_TP") (pintype "input"))
      (node (ref "U$2") (pin "2") (pinfunction "2_2") (pintype "bidirectional"))
    )
    (net (code "49") (name "SCLK") (class "Default")
      (node (ref "IC1") (pin "31") (pinfunction "SCLK_31") (pintype "bidirectional"))
      (node (ref "J3") (pin "5") (pinfunction "5_5") (pintype "passive"))
      (node (ref "U$2") (pin "7") (pinfunction "7_7") (pintype "bidirectional"))
    )
    (net (code "50") (name "SLA") (class "Default")
      (node (ref "IC1") (pin "11") (pinfunction "SLA_11") (pintype "bidirectional"))
      (node (ref "U$3") (pin "SLA") (pinfunction "SLA_SLA") (pintype "bidirectional"))
      (node (ref "U$3") (pin "SLAH") (pinfunction "SLA_SLAH") (pintype "bidirectional"))
    )
    (net (code "51") (name "SLB") (class "Default")
      (node (ref "IC1") (pin "14") (pinfunction "SLB_14") (pintype "bidirectional"))
      (node (ref "U$3") (pin "SLB") (pinfunction "SLB_SLB") (pintype "bidirectional"))
      (node (ref "U$3") (pin "SLBH") (pinfunction "SLB_SLBH") (pintype "bidirectional"))
    )
    (net (code "52") (name "SLC") (class "Default")
      (node (ref "IC1") (pin "21") (pinfunction "SLC_21") (pintype "bidirectional"))
      (node (ref "U$3") (pin "SLC") (pinfunction "SLC_SLC") (pintype "bidirectional"))
      (node (ref "U$3") (pin "SLCH") (pinfunction "SLC_SLCH") (pintype "bidirectional"))
    )
    (net (code "53") (name "SOA") (class "Default")
      (node (ref "R10") (pin "2") (pinfunction "2_2") (pintype "passive"))
      (node (ref "U$3") (pin "SOA") (pinfunction "SOA_SOA") (pintype "bidirectional"))
      (node (ref "U$3") (pin "SOAH") (pinfunction "SOA_SOAH") (pintype "bidirectional"))
    )
    (net (code "54") (name "SOB") (class "Default")
      (node (ref "R11") (pin "2") (pinfunction "2_2") (pintype "passive"))
      (node (ref "U$3") (pin "SOB") (pinfunction "SOB_SOB") (pintype "bidirectional"))
      (node (ref "U$3") (pin "SOBH") (pinfunction "SOB_SOBH") (pintype "bidirectional"))
    )
    (net (code "55") (name "SOC") (class "Default")
      (node (ref "R12") (pin "2") (pinfunction "2_2") (pintype "passive"))
      (node (ref "U$3") (pin "SOC") (pinfunction "SOC_SOC") (pintype "bidirectional"))
      (node (ref "U$3") (pin "SOCH") (pinfunction "SOC_SOCH") (pintype "bidirectional"))
    )
    (net (code "56") (name "VBUCK") (class "Default")
      (node (ref "C19") (pin "1") (pinfunction "1_1") (pintype "passive"))
      (node (ref "C20") (pin "2") (pinfunction "2_2") (pintype "passive"))
      (node (ref "C27") (pin "2") (pinfunction "2_2") (pintype "passive"))
      (node (ref "L3") (pin "P$1") (pinfunction "1_P$1") (pintype "passive"))
      (node (ref "LDO") (pin "1") (pinfunction "IN_1") (pintype "input"))
      (node (ref "LDO") (pin "3") (pinfunction "ON/~{OFF}_3") (pintype "bidirectional"))
      (node (ref "R_FB1") (pin "2") (pinfunction "2_2") (pintype "passive"))
      (node (ref "SV1") (pin "1") (pinfunction "1_1") (pintype "passive"))
      (node (ref "U$1") (pin "LINE") (pinfunction "LINE_LINE") (pintype "passive"))
    )
    (net (code "57") (name "VDRAIN") (class "Default")
      (node (ref "C13") (pin "1") (pinfunction "1_1") (pintype "passive"))
      (node (ref "C14") (pin "2") (pinfunction "2_2") (pintype "passive"))
      (node (ref "C22") (pin "1") (pinfunction "1_1") (pintype "passive"))
      (node (ref "IC1") (pin "43") (pinfunction "VIN_43") (pintype "bidirectional"))
      (node (ref "IC1") (pin "6") (pinfunction "VDRAIN_6") (pintype "bidirectional"))
      (node (ref "R14") (pin "1") (pinfunction "1_1") (pintype "passive"))
      (node (ref "R18") (pin "2") (pinfunction "2_2") (pintype "passive"))
      (node (ref "SV1") (pin "3") (pinfunction "3_3") (pintype "passive"))
      (node (ref "U$3") (pin "VDRAIN") (pinfunction "VDRAIN_VDRAIN") (pintype "bidirectional"))
      (node (ref "U$3") (pin "VDRAIN2") (pinfunction "VDRAIN2_VDRAIN2") (pintype "bidirectional"))
      (node (ref "U$3") (pin "VDRAIN2H") (pinfunction "VDRAIN2_VDRAIN2H") (pintype "bidirectional"))
      (node (ref "U$3") (pin "VDRAINH1") (pinfunction "VDRAIN_VDRAINH1") (pintype "bidirectional"))
      (node (ref "U$3") (pin "VDRAINH2") (pinfunction "VDRAIN_VDRAINH2") (pintype "bidirectional"))
      (node (ref "U$3") (pin "VDRAINH3") (pinfunction "VDRAIN_VDRAINH3") (pintype "bidirectional"))
      (node (ref "U$3") (pin "VDRAINH4") (pinfunction "VDRAIN_VDRAINH4") (pintype "bidirectional"))
    )
    (net (code "58") (name "VSENA") (class "Default")
      (node (ref "C34") (pin "1") (pinfunction "1_1") (pintype "passive"))
      (node (ref "R24") (pin "1") (pinfunction "1_1") (pintype "passive"))
      (node (ref "R25") (pin "2") (pinfunction "2_2") (pintype "passive"))
      (node (ref "TVS_DIODE") (pin "D1+") (pinfunction "D2+_D1+") (pintype "bidirectional"))
      (node (ref "TVS_DIODE") (pin "P$6") (pinfunction "NC2_P$6") (pintype "bidirectional"))
      (node (ref "U$2") (pin "30") (pinfunction "30_30") (pintype "bidirectional"))
    )
    (net (code "59") (name "VSENB") (class "Default")
      (node (ref "C35") (pin "1") (pinfunction "1_1") (pintype "passive"))
      (node (ref "R26") (pin "2") (pinfunction "2_2") (pintype "passive"))
      (node (ref "R27") (pin "1") (pinfunction "1_1") (pintype "passive"))
      (node (ref "TVS_DIODE") (pin "D0-") (pinfunction "D1-_D0-") (pintype "bidirectional"))
      (node (ref "TVS_DIODE") (pin "P$7") (pinfunction "NC3_P$7") (pintype "bidirectional"))
      (node (ref "U$2") (pin "25") (pinfunction "25_25") (pintype "bidirectional"))
    )
    (net (code "60") (name "VSENC") (class "Default")
      (node (ref "C36") (pin "1") (pinfunction "1_1") (pintype "passive"))
      (node (ref "R28") (pin "1") (pinfunction "1_1") (pintype "passive"))
      (node (ref "R29") (pin "2") (pinfunction "2_2") (pintype "passive"))
      (node (ref "TVS_DIODE") (pin "D0+") (pinfunction "D1+_D0+") (pintype "bidirectional"))
      (node (ref "TVS_DIODE") (pin "P$8") (pinfunction "NC4_P$8") (pintype "bidirectional"))
      (node (ref "U$2") (pin "26") (pinfunction "26_26") (pintype "bidirectional"))
    )
    (net (code "61") (name "VSENVM") (class "Default")
      (node (ref "C24") (pin "1") (pinfunction "1_1") (pintype "passive"))
      (node (ref "R18") (pin "1") (pinfunction "1_1") (pintype "passive"))
      (node (ref "R19") (pin "2") (pinfunction "2_2") (pintype "passive"))
      (node (ref "TVS_DIODE") (pin "D1-") (pinfunction "D2-_D1-") (pintype "bidirectional"))
      (node (ref "TVS_DIODE") (pin "P$5") (pinfunction "NC1_P$5") (pintype "bidirectional"))
      (node (ref "U$2") (pin "23") (pinfunction "23_23") (pintype "bidirectional"))
    )
    (net (code "62") (name "unconnected-(IC1-NC1-Pad24)") (class "Default")
      (node (ref "IC1") (pin "24") (pinfunction "NC1_24") (pintype "bidirectional"))
    )
    (net (code "63") (name "unconnected-(IC1-NC2-Pad23)") (class "Default")
      (node (ref "IC1") (pin "23") (pinfunction "NC2_23") (pintype "bidirectional"))
    )
    (net (code "64") (name "unconnected-(IC1-NC3-Pad22)") (class "Default")
      (node (ref "IC1") (pin "22") (pinfunction "NC3_22") (pintype "bidirectional"))
    )
    (net (code "65") (name "unconnected-(IC1-NC4-Pad13)") (class "Default")
      (node (ref "IC1") (pin "13") (pinfunction "NC4_13") (pintype "bidirectional"))
    )
    (net (code "66") (name "unconnected-(IC1-NC5-Pad12)") (class "Default")
      (node (ref "IC1") (pin "12") (pinfunction "NC5_12") (pintype "bidirectional"))
    )
    (net (code "67") (name "unconnected-(IC1-NC6-Pad25)") (class "Default")
      (node (ref "IC1") (pin "25") (pinfunction "NC6_25") (pintype "bidirectional"))
    )
    (net (code "68") (name "unconnected-(IC1-NC7-Pad26)") (class "Default")
      (node (ref "IC1") (pin "26") (pinfunction "NC7_26") (pintype "bidirectional"))
    )
    (net (code "69") (name "unconnected-(J4-Pad1)") (class "Default")
      (node (ref "J4") (pin "1") (pinfunction "1_1") (pintype "bidirectional"))
    )
    (net (code "70") (name "unconnected-(U$2-Pad3)") (class "Default")
      (node (ref "U$2") (pin "3") (pinfunction "3_3") (pintype "bidirectional"))
    )
    (net (code "71") (name "unconnected-(U$2-Pad4)") (class "Default")
      (node (ref "U$2") (pin "4") (pinfunction "4_4") (pintype "bidirectional"))
    )
    (net (code "72") (name "unconnected-(U$2-Pad5)") (class "Default")
      (node (ref "U$2") (pin "5") (pinfunction "5_5") (pintype "bidirectional"))
    )
    (net (code "73") (name "unconnected-(U$2-Pad6)") (class "Default")
      (node (ref "U$2") (pin "6") (pinfunction "6_6") (pintype "bidirectional"))
    )
    (net (code "74") (name "unconnected-(U$2-Pad8)") (class "Default")
      (node (ref "U$2") (pin "8") (pinfunction "8_8") (pintype "bidirectional"))
    )
    (net (code "75") (name "unconnected-(U$2-Pad9)") (class "Default")
      (node (ref "U$2") (pin "9") (pinfunction "9_9") (pintype "bidirectional"))
    )
    (net (code "76") (name "unconnected-(U$2-Pad10)") (class "Default")
      (node (ref "U$2") (pin "10") (pinfunction "10_10") (pintype "bidirectional"))
    )
    (net (code "77") (name "unconnected-(U$2-Pad13)") (class "Default")
      (node (ref "U$2") (pin "13") (pinfunction "13_13") (pintype "bidirectional"))
    )
    (net (code "78") (name "unconnected-(U$2-Pad16)") (class "Default")
      (node (ref "U$2") (pin "16") (pinfunction "16_16") (pintype "bidirectional"))
    )
    (net (code "79") (name "unconnected-(U$2-Pad17)") (class "Default")
      (node (ref "U$2") (pin "17") (pinfunction "17_17") (pintype "bidirectional"))
    )
    (net (code "80") (name "unconnected-(U$2-Pad18)") (class "Default")
      (node (ref "U$2") (pin "18") (pinfunction "18_18") (pintype "bidirectional"))
    )
    (net (code "81") (name "unconnected-(U$2-Pad24)") (class "Default")
      (node (ref "U$2") (pin "24") (pinfunction "24_24") (pintype "bidirectional"))
    )
    (net (code "82") (name "unconnected-(U$2-Pad31)") (class "Default")
      (node (ref "U$2") (pin "31") (pinfunction "31_31") (pintype "bidirectional"))
    )
  )
)
